# Adafruit_MCP9600.net
KiCad netlist of a schematic drawn in EAGLE
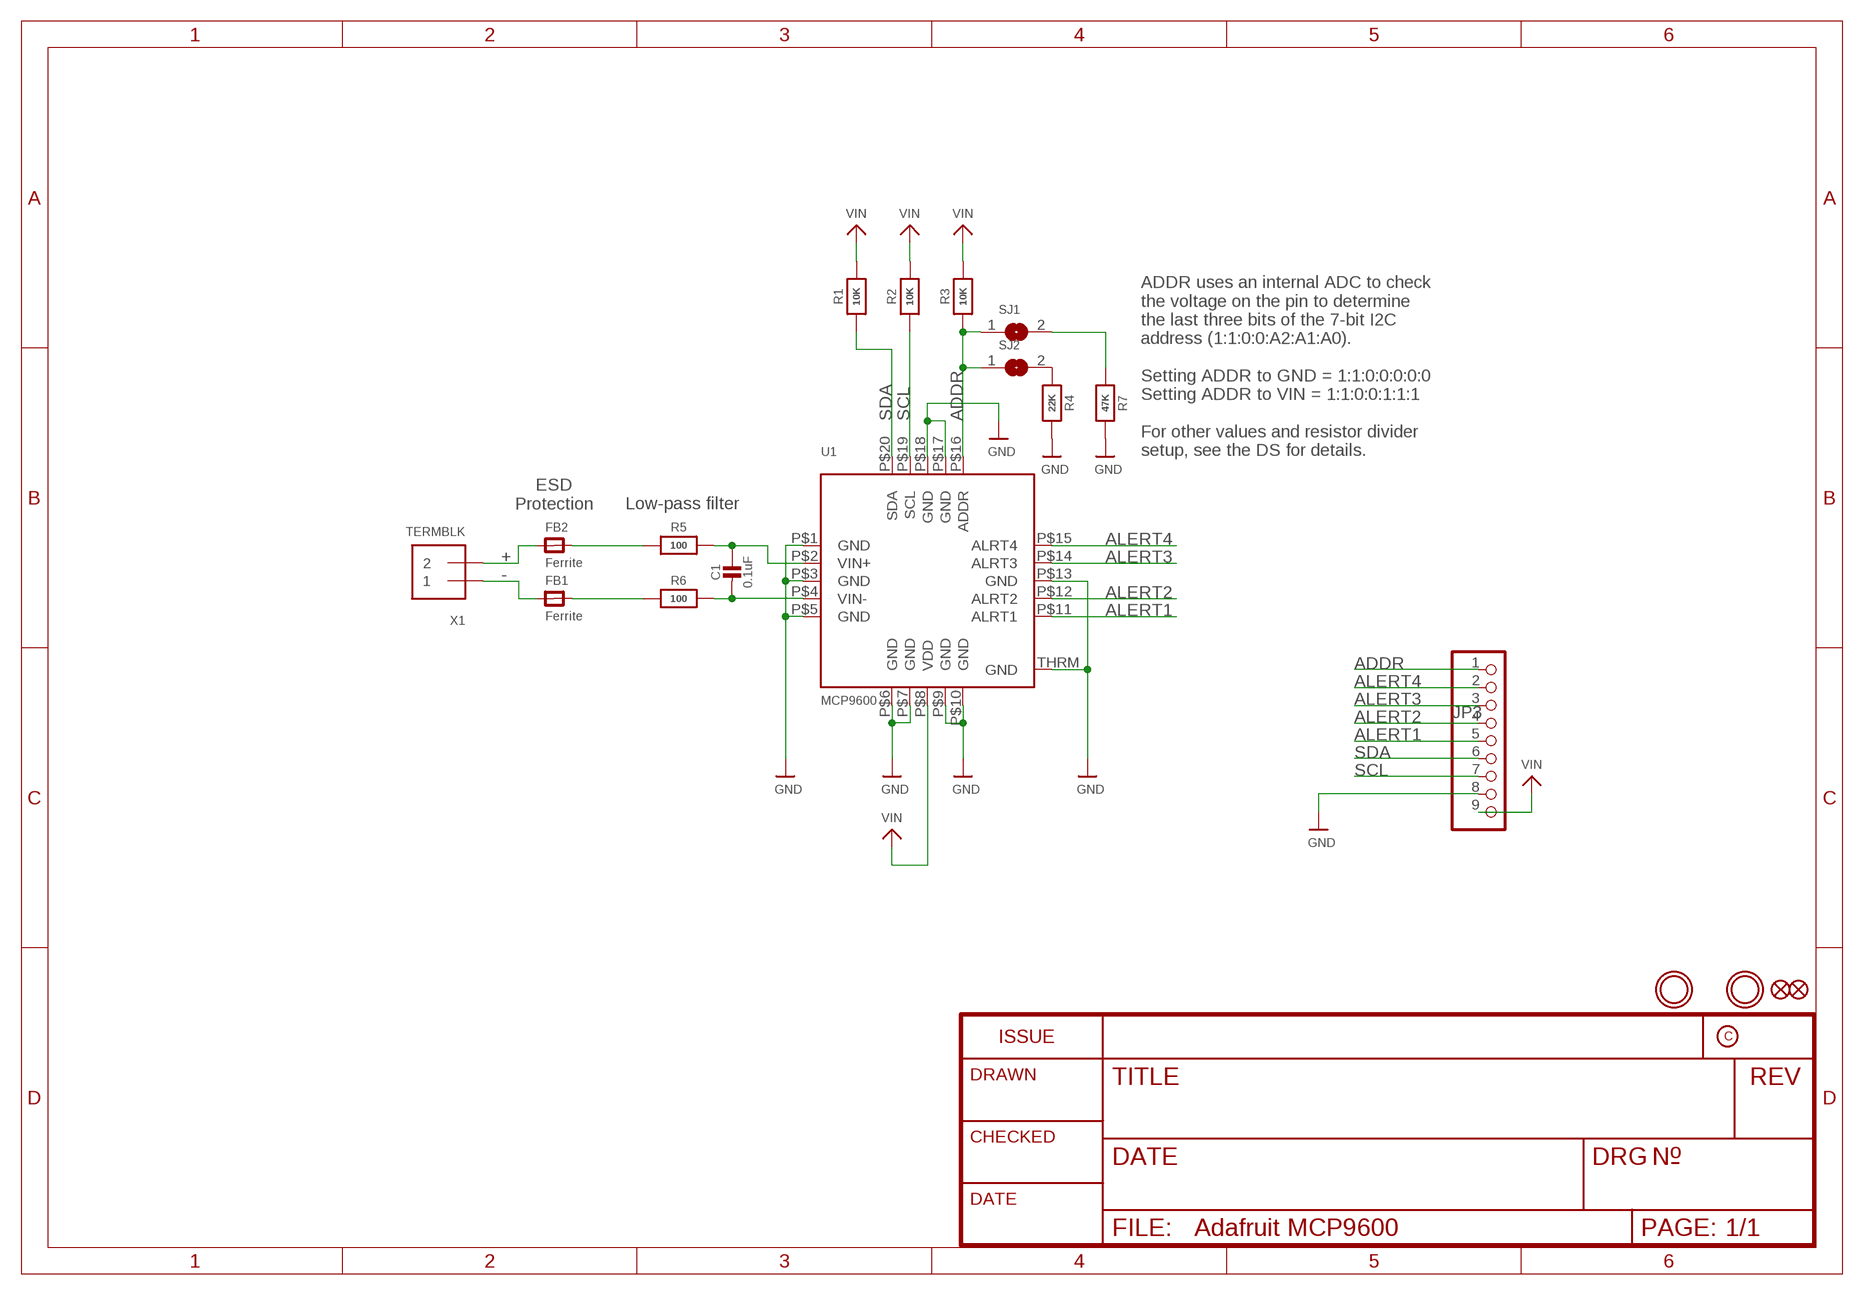
[diagram p0: schematic, sheet 1]

(export (version "E")
  (design (tool "Eeschema 10.0.6"))
  (components
    (comp (ref "C1")
      (value "0.1uF")
      (footprint "eagle-import:0603-NO")
      (libsource (lib "eagle-import") (part "CAP_CERAMIC0603_NO"))
    )
    (comp (ref "FB1")
      (value "Ferrite")
      (footprint "eagle-import:0805-NO")
      (libsource (lib "eagle-import") (part "FERRITE-0805NO"))
    )
    (comp (ref "FB2")
      (value "Ferrite")
      (footprint "eagle-import:0805-NO")
      (libsource (lib "eagle-import") (part "FERRITE-0805NO"))
    )
    (comp (ref "FID1")
      (value "FIDUCIAL_1MM")
      (footprint "eagle-import:FIDUCIAL_1MM")
      (libsource (lib "eagle-import") (part "FIDUCIAL_1MM"))
    )
    (comp (ref "FID2")
      (value "FIDUCIAL_1MM")
      (footprint "eagle-import:FIDUCIAL_1MM")
      (libsource (lib "eagle-import") (part "FIDUCIAL_1MM"))
    )
    (comp (ref "JP3")
      (value "HEADER-1X970MIL")
      (footprint "eagle-import:1X09_ROUND_70")
      (libsource (lib "eagle-import") (part "HEADER-1X970MIL"))
    )
    (comp (ref "R1")
      (value "10K")
      (footprint "eagle-import:0603-NO")
      (libsource (lib "eagle-import") (part "RESISTOR_0603_NOOUT"))
    )
    (comp (ref "R2")
      (value "10K")
      (footprint "eagle-import:0603-NO")
      (libsource (lib "eagle-import") (part "RESISTOR_0603_NOOUT"))
    )
    (comp (ref "R3")
      (value "10K")
      (footprint "eagle-import:0603-NO")
      (libsource (lib "eagle-import") (part "RESISTOR_0603_NOOUT"))
    )
    (comp (ref "R4")
      (value "22K")
      (footprint "eagle-import:0603-NO")
      (libsource (lib "eagle-import") (part "RESISTOR_0603_NOOUT"))
    )
    (comp (ref "R5")
      (value "100")
      (footprint "eagle-import:0603-NO")
      (libsource (lib "eagle-import") (part "RESISTOR_0603_NOOUT"))
    )
    (comp (ref "R6")
      (value "100")
      (footprint "eagle-import:0603-NO")
      (libsource (lib "eagle-import") (part "RESISTOR_0603_NOOUT"))
    )
    (comp (ref "R7")
      (value "47K")
      (footprint "eagle-import:0603-NO")
      (libsource (lib "eagle-import") (part "RESISTOR_0603_NOOUT"))
    )
    (comp (ref "SJ1")
      (value "SOLDERJUMPER")
      (footprint "eagle-import:SOLDERJUMPER_ARROW_NOPASTE")
      (libsource (lib "eagle-import") (part "SOLDERJUMPER"))
    )
    (comp (ref "SJ2")
      (value "SOLDERJUMPER")
      (footprint "eagle-import:SOLDERJUMPER_ARROW_NOPASTE")
      (libsource (lib "eagle-import") (part "SOLDERJUMPER"))
    )
    (comp (ref "U$1")
      (value "MOUNTINGHOLE2.5")
      (footprint "eagle-import:MOUNTINGHOLE_2.5_PLATED")
      (libsource (lib "eagle-import") (part "MOUNTINGHOLE2.5"))
    )
    (comp (ref "U$3")
      (value "MOUNTINGHOLE2.5")
      (footprint "eagle-import:MOUNTINGHOLE_2.5_PLATED")
      (libsource (lib "eagle-import") (part "MOUNTINGHOLE2.5"))
    )
    (comp (ref "U1")
      (value "MCP9600")
      (footprint "eagle-import:VQFN20_5MM")
      (libsource (lib "eagle-import") (part "MCP9600"))
    )
    (comp (ref "X1")
      (value "TERMBLK")
      (footprint "eagle-import:TERMBLOCK_1X2-3.5MM")
      (libsource (lib "eagle-import") (part "TERMBLOCK_1X2_3.5MM"))
    )
  )
  (nets
    (net (code "1") (name "/+") (class "Default")
      (node (ref "FB2") (pin "1") (pinfunction "P$1_1") (pintype "passive"))
      (node (ref "X1") (pin "2") (pinfunction "2_2") (pintype "passive"))
    )
    (net (code "2") (name "/-") (class "Default")
      (node (ref "FB1") (pin "1") (pinfunction "P$1_1") (pintype "passive"))
      (node (ref "X1") (pin "1") (pinfunction "1_1") (pintype "passive"))
    )
    (net (code "3") (name "/ADDR") (class "Default")
      (node (ref "JP3") (pin "1") (pinfunction "1_1") (pintype "passive"))
      (node (ref "R3") (pin "1") (pinfunction "1_1") (pintype "passive"))
      (node (ref "SJ1") (pin "1") (pinfunction "1_1") (pintype "passive"))
      (node (ref "SJ2") (pin "1") (pinfunction "1_1") (pintype "passive"))
      (node (ref "U1") (pin "P$16") (pinfunction "ADDR_P$16") (pintype "bidirectional"))
    )
    (net (code "4") (name "/ALERT1") (class "Default")
      (node (ref "JP3") (pin "5") (pinfunction "5_5") (pintype "passive"))
      (node (ref "U1") (pin "P$11") (pinfunction "ALRT1_P$11") (pintype "bidirectional"))
    )
    (net (code "5") (name "/ALERT2") (class "Default")
      (node (ref "JP3") (pin "4") (pinfunction "4_4") (pintype "passive"))
      (node (ref "U1") (pin "P$12") (pinfunction "ALRT2_P$12") (pintype "bidirectional"))
    )
    (net (code "6") (name "/ALERT3") (class "Default")
      (node (ref "JP3") (pin "3") (pinfunction "3_3") (pintype "passive"))
      (node (ref "U1") (pin "P$14") (pinfunction "ALRT3_P$14") (pintype "bidirectional"))
    )
    (net (code "7") (name "/ALERT4") (class "Default")
      (node (ref "JP3") (pin "2") (pinfunction "2_2") (pintype "passive"))
      (node (ref "U1") (pin "P$15") (pinfunction "ALRT4_P$15") (pintype "bidirectional"))
    )
    (net (code "8") (name "/SCL") (class "Default")
      (node (ref "JP3") (pin "7") (pinfunction "7_7") (pintype "passive"))
      (node (ref "R2") (pin "1") (pinfunction "1_1") (pintype "passive"))
      (node (ref "U1") (pin "P$19") (pinfunction "SCL_P$19") (pintype "bidirectional"))
    )
    (net (code "9") (name "/SDA") (class "Default")
      (node (ref "JP3") (pin "6") (pinfunction "6_6") (pintype "passive"))
      (node (ref "R1") (pin "1") (pinfunction "1_1") (pintype "passive"))
      (node (ref "U1") (pin "P$20") (pinfunction "SDA_P$20") (pintype "bidirectional"))
    )
    (net (code "10") (name "GND") (class "Default")
      (node (ref "JP3") (pin "8") (pinfunction "8_8") (pintype "passive"))
      (node (ref "R4") (pin "2") (pinfunction "2_2") (pintype "passive"))
      (node (ref "R7") (pin "2") (pinfunction "2_2") (pintype "passive"))
      (node (ref "U1") (pin "P$1") (pinfunction "GND_P$1") (pintype "bidirectional"))
      (node (ref "U1") (pin "P$10") (pinfunction "GND_P$10") (pintype "bidirectional"))
      (node (ref "U1") (pin "P$13") (pinfunction "GND_P$13") (pintype "bidirectional"))
      (node (ref "U1") (pin "P$17") (pinfunction "GND_P$17") (pintype "bidirectional"))
      (node (ref "U1") (pin "P$18") (pinfunction "GND_P$18") (pintype "bidirectional"))
      (node (ref "U1") (pin "P$3") (pinfunction "GND_P$3") (pintype "bidirectional"))
      (node (ref "U1") (pin "P$5") (pinfunction "GND_P$5") (pintype "bidirectional"))
      (node (ref "U1") (pin "P$6") (pinfunction "GND_P$6") (pintype "bidirectional"))
      (node (ref "U1") (pin "P$7") (pinfunction "GND_P$7") (pintype "bidirectional"))
      (node (ref "U1") (pin "P$9") (pinfunction "GND_P$9") (pintype "bidirectional"))
      (node (ref "U1") (pin "THRM") (pinfunction "GND_THRM") (pintype "bidirectional"))
    )
    (net (code "11") (name "Net-(FB1-P$2)") (class "Default")
      (node (ref "FB1") (pin "2") (pinfunction "P$2_2") (pintype "passive"))
      (node (ref "R6") (pin "1") (pinfunction "1_1") (pintype "passive"))
    )
    (net (code "12") (name "Net-(FB2-P$2)") (class "Default")
      (node (ref "FB2") (pin "2") (pinfunction "P$2_2") (pintype "passive"))
      (node (ref "R5") (pin "1") (pinfunction "1_1") (pintype "passive"))
    )
    (net (code "13") (name "Net-(R4-Pad1)") (class "Default")
      (node (ref "R4") (pin "1") (pinfunction "1_1") (pintype "passive"))
      (node (ref "SJ2") (pin "2") (pinfunction "2_2") (pintype "passive"))
    )
    (net (code "14") (name "Net-(R7-Pad1)") (class "Default")
      (node (ref "R7") (pin "1") (pinfunction "1_1") (pintype "passive"))
      (node (ref "SJ1") (pin "2") (pinfunction "2_2") (pintype "passive"))
    )
    (net (code "15") (name "Net-(U1-VIN+)") (class "Default")
      (node (ref "C1") (pin "1") (pinfunction "1_1") (pintype "passive"))
      (node (ref "R5") (pin "2") (pinfunction "2_2") (pintype "passive"))
      (node (ref "U1") (pin "P$2") (pinfunction "VIN+_P$2") (pintype "bidirectional"))
    )
    (net (code "16") (name "Net-(U1-VIN-)") (class "Default")
      (node (ref "C1") (pin "2") (pinfunction "2_2") (pintype "passive"))
      (node (ref "R6") (pin "2") (pinfunction "2_2") (pintype "passive"))
      (node (ref "U1") (pin "P$4") (pinfunction "VIN-_P$4") (pintype "bidirectional"))
    )
    (net (code "17") (name "VIN") (class "Default")
      (node (ref "JP3") (pin "9") (pinfunction "9_9") (pintype "passive"))
      (node (ref "R1") (pin "2") (pinfunction "2_2") (pintype "passive"))
      (node (ref "R2") (pin "2") (pinfunction "2_2") (pintype "passive"))
      (node (ref "R3") (pin "2") (pinfunction "2_2") (pintype "passive"))
      (node (ref "U1") (pin "P$8") (pinfunction "VDD_P$8") (pintype "bidirectional"))
    )
  )
)
